# Filter_Capacitors_-_ADC_Sensor.net
KiCad netlist of a schematic drawn in Altium Designer
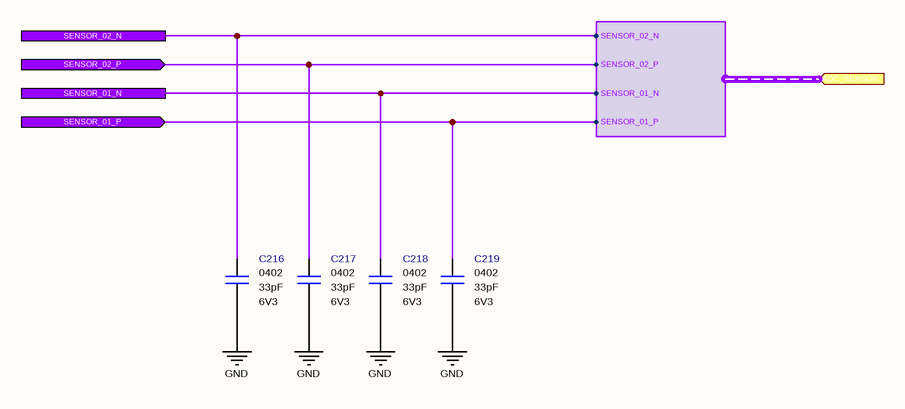
[diagram p0: Filter Capacitors - ADC Sensor.SchDoc]

(export (version "E")
  (design (tool "Eeschema 10.0.6"))
  (components
    (comp (ref "C216")
      (value "33pF")
      (footprint "CAPACITOR_0402")
      (description "Capacitor - 33pF [0402] (Ceramic)")
      (fields
        (field (name "TOLERANCE") "10%")
        (field (name "CASE") "0402")
        (field (name "VOLTAGE") "6V3")
        (field (name "MANUFACTURER PART NUMBER") "C0402C330J9RACAUTO")
      )
      (libsource (lib "Ovoo_Library") (part "Capacitor - 33pF [0402-6V3]"))
    )
    (comp (ref "C217")
      (value "33pF")
      (footprint "CAPACITOR_0402")
      (description "Capacitor - 33pF [0402] (Ceramic)")
      (fields
        (field (name "TOLERANCE") "10%")
        (field (name "CASE") "0402")
        (field (name "VOLTAGE") "6V3")
        (field (name "MANUFACTURER PART NUMBER") "C0402C330J9RACAUTO")
      )
      (libsource (lib "Ovoo_Library") (part "Capacitor - 33pF [0402-6V3]"))
    )
    (comp (ref "C218")
      (value "33pF")
      (footprint "CAPACITOR_0402")
      (description "Capacitor - 33pF [0402] (Ceramic)")
      (fields
        (field (name "TOLERANCE") "10%")
        (field (name "CASE") "0402")
        (field (name "VOLTAGE") "6V3")
        (field (name "MANUFACTURER PART NUMBER") "C0402C330J9RACAUTO")
      )
      (libsource (lib "Ovoo_Library") (part "Capacitor - 33pF [0402-6V3]"))
    )
    (comp (ref "C219")
      (value "33pF")
      (footprint "CAPACITOR_0402")
      (description "Capacitor - 33pF [0402] (Ceramic)")
      (fields
        (field (name "TOLERANCE") "10%")
        (field (name "CASE") "0402")
        (field (name "VOLTAGE") "6V3")
        (field (name "MANUFACTURER PART NUMBER") "C0402C330J9RACAUTO")
      )
      (libsource (lib "Ovoo_Library") (part "Capacitor - 33pF [0402-6V3]"))
    )
  )
  (nets
    (net (code "2") (name "/SENSOR_01_N") (class "Default")
      (node (ref "C218") (pin "2") (pinfunction "2_2") (pintype "passive"))
    )
    (net (code "3") (name "/SENSOR_01_P") (class "Default")
      (node (ref "C219") (pin "2") (pinfunction "2_2") (pintype "passive"))
    )
    (net (code "4") (name "/SENSOR_02_N") (class "Default")
      (node (ref "C216") (pin "2") (pinfunction "2_2") (pintype "passive"))
    )
    (net (code "5") (name "/SENSOR_02_P") (class "Default")
      (node (ref "C217") (pin "2") (pinfunction "2_2") (pintype "passive"))
    )
    (net (code "7") (name "GND") (class "Default")
      (node (ref "C216") (pin "1") (pinfunction "1_1") (pintype "passive"))
      (node (ref "C217") (pin "1") (pinfunction "1_1") (pintype "passive"))
      (node (ref "C218") (pin "1") (pinfunction "1_1") (pintype "passive"))
      (node (ref "C219") (pin "1") (pinfunction "1_1") (pintype "passive"))
    )
  )
)
